# S7CAS-PLEIADES-CARTE-MERE_P01_FPGA-BANK4.net
KiCad netlist of a schematic drawn in Altium Designer
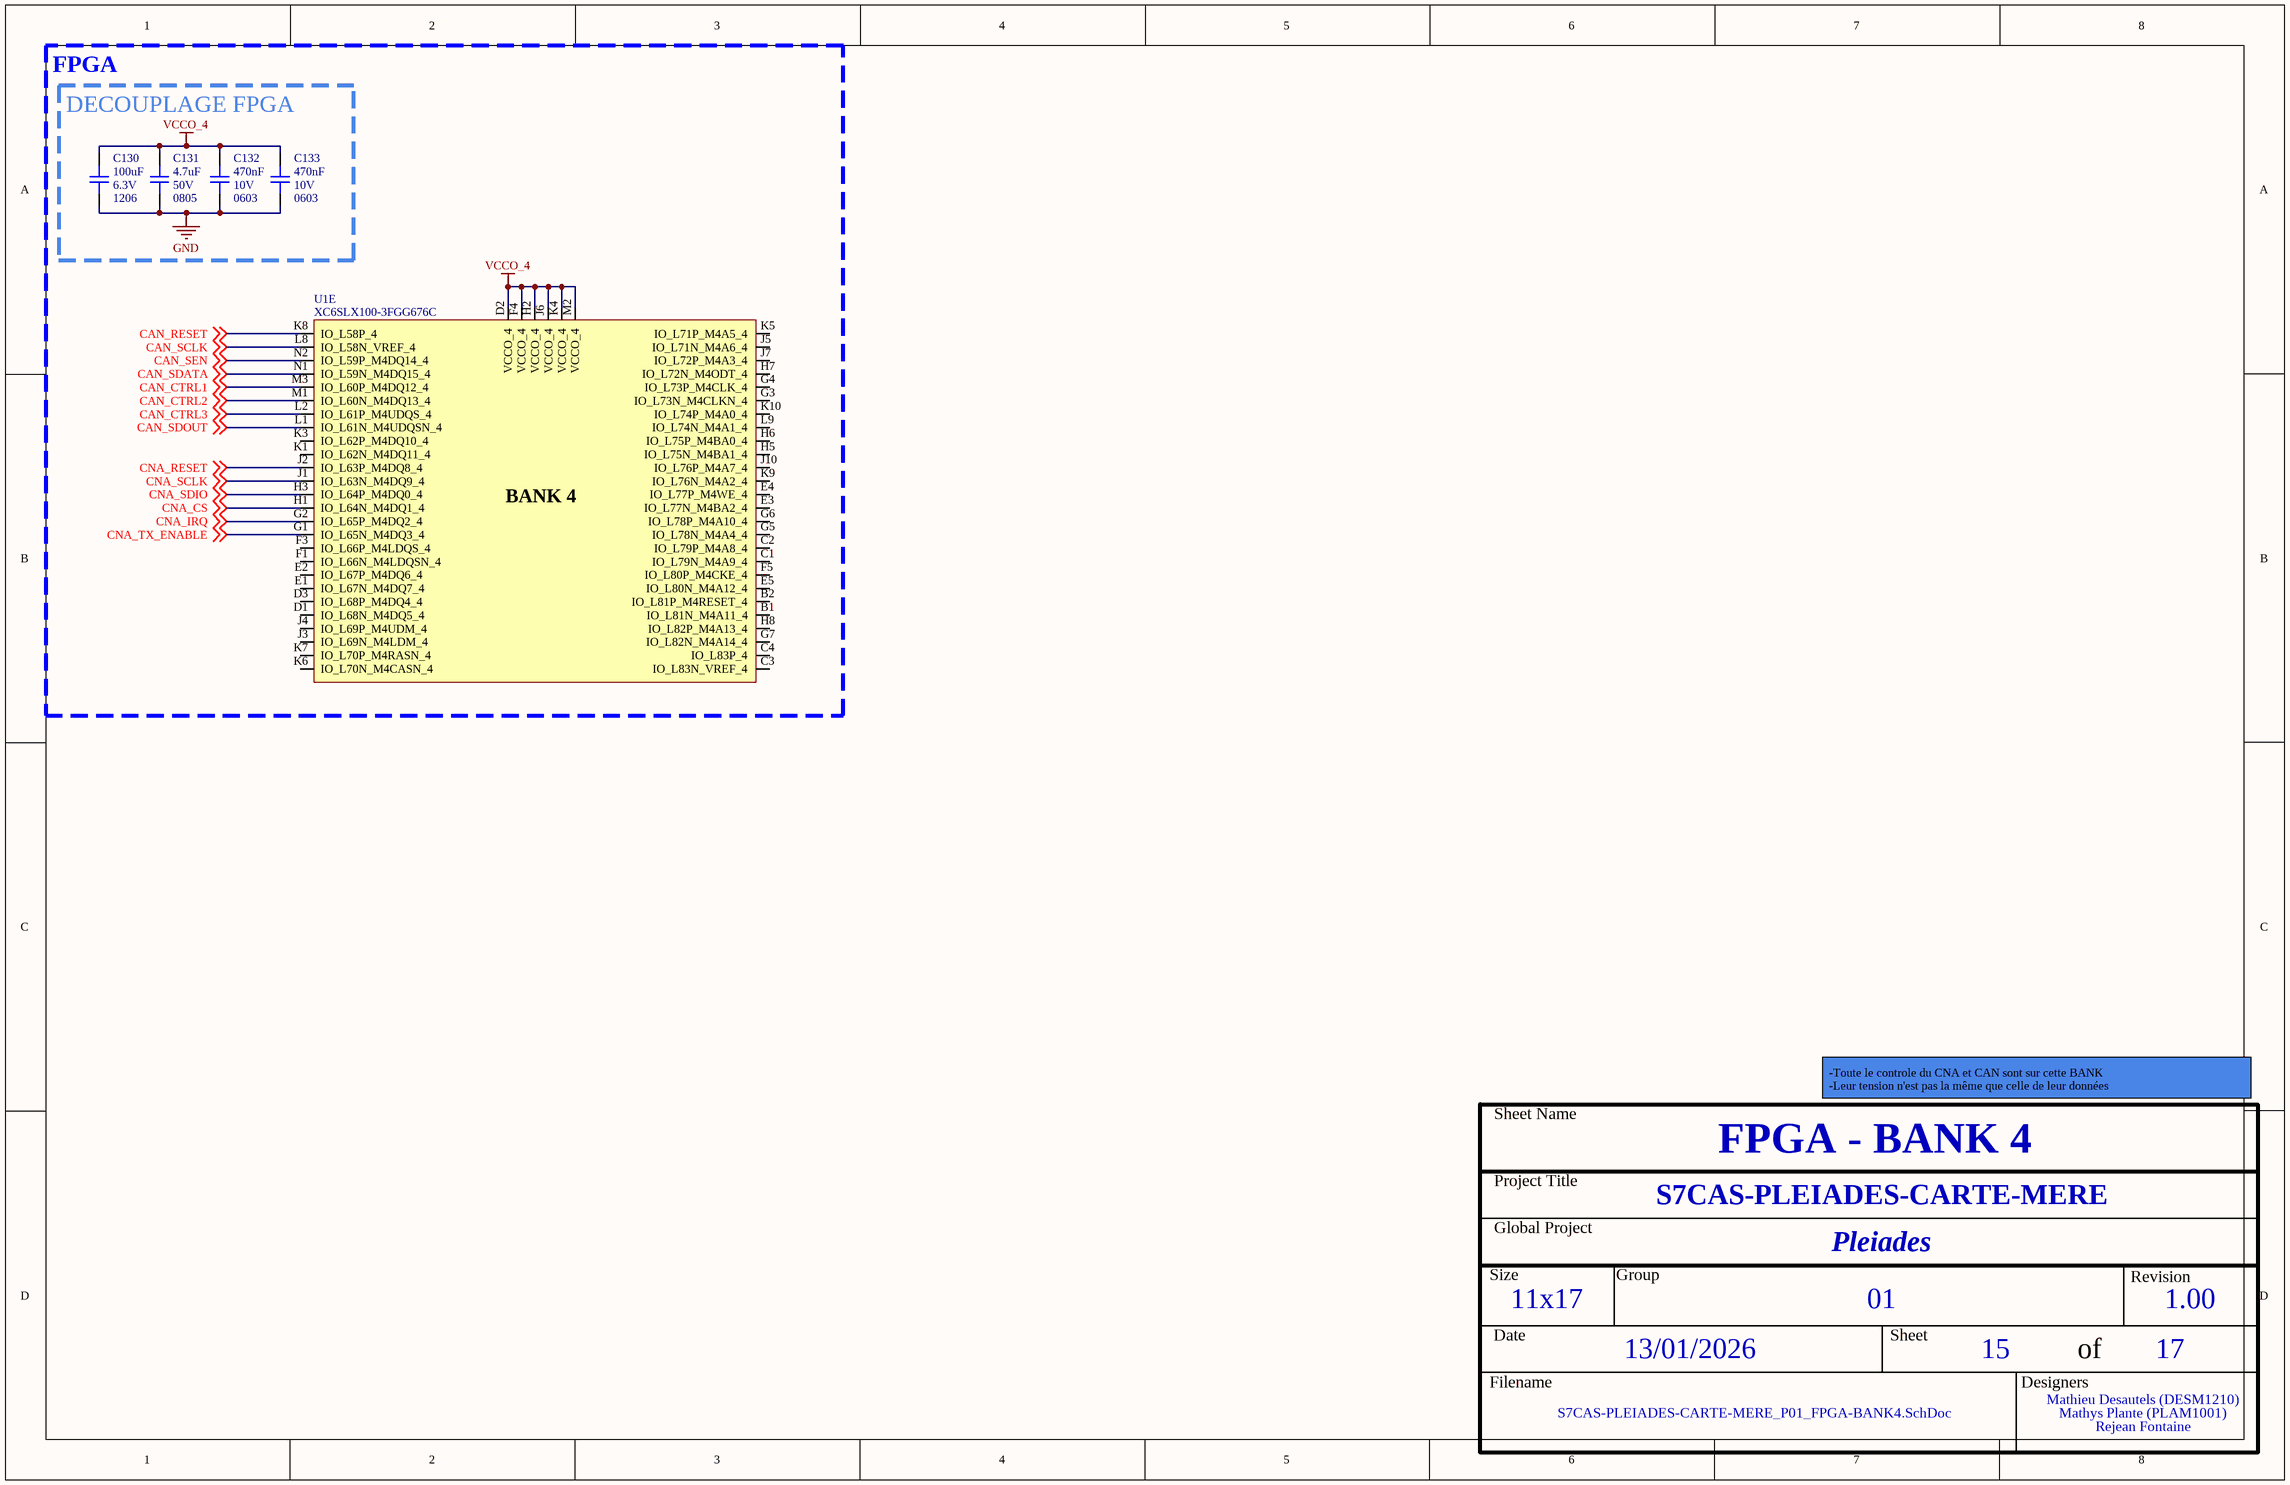
[diagram p0: S7CAS-PLEIADES-CARTE-MERE_P01_FPGA-BANK4.SchDoc]

(export (version "E")
  (design (tool "Eeschema 10.0.6"))
  (components
    (comp (ref "C130")
      (value "100uF")
      (footprint "CAP_1206")
      (description "100 µF ±20% 6.3V Ceramic Capacitor X6T 1206 (3216 Metric)")
      (fields
        (field (name "MFG") "Murata Electronics")
        (field (name "MFG PART NUMBER") "GRM31CD80J107MEA8K")
        (field (name "VOLTAGE") "6.3V")
        (field (name "PACKAGE") "1206")
        (field (name "CREATEDBY") "Jonathan Bouchard")
      )
      (libsource (lib "s7cas_lib2023") (part "CAP - 1206"))
    )
    (comp (ref "C131")
      (value "4.7uF")
      (footprint "CAP_0805")
      (description "4.7 µF ±10% 50V Ceramic Capacitor X5R 0805 (2012 Metric)")
      (fields
        (field (name "MFG") "Murata Electronics")
        (field (name "MFG PART NUMBER") "GRT21BR61H475KE13L")
        (field (name "VOLTAGE") "50V")
        (field (name "PACKAGE") "0805")
        (field (name "CREATEDBY") "Jonathan Bouchard")
      )
      (libsource (lib "s7cas_lib2023") (part "CAP - 0805"))
    )
    (comp (ref "C132")
      (value "470nF")
      (footprint "CAP_0603")
      (description "CAP - 0603")
      (fields
        (field (name "MFG PART NUMBER") "C0603X474K8RAC")
        (field (name "VOLTAGE") "10V")
        (field (name "PACKAGE") "0603")
        (field (name "CREATEDBY") "Jonathan Bouchard")
      )
      (libsource (lib "s7cas_lib2023") (part "CAP - 0603"))
    )
    (comp (ref "C133")
      (value "470nF")
      (footprint "CAP_0603")
      (description "CAP - 0603")
      (fields
        (field (name "MFG PART NUMBER") "C0603X474K8RAC")
        (field (name "VOLTAGE") "10V")
        (field (name "PACKAGE") "0603")
        (field (name "CREATEDBY") "Jonathan Bouchard")
      )
      (libsource (lib "s7cas_lib2023") (part "CAP - 0603"))
    )
    (comp (ref "U1")
      (value "XC6SLX100-3FGG676C")
      (footprint "FPGA_XILINX_FGG676")
      (description "FPGA - XILINX SPARTAN 6 480 I/O - BGA-676")
      (fields
        (field (name "VOLTAGE") "1.14 V ~ 1.26 V")
        (field (name "MFG") "Xilinx")
        (field (name "CREATEDBY") "Jonathan Bouchard")
      )
      (libsource (lib "s7cas_lib2023") (part "FPGA_XC6SLX100-3FGG676C"))
    )
  )
  (nets
    (net (code "1") (name "CAN_CTRL1") (class "Default")
      (node (ref "U1") (pin "M3") (pinfunction "IO_L60P_M4DQ12_4_M3") (pintype "passive"))
    )
    (net (code "2") (name "CAN_CTRL2") (class "Default")
      (node (ref "U1") (pin "M1") (pinfunction "IO_L60N_M4DQ13_4_M1") (pintype "passive"))
    )
    (net (code "3") (name "CAN_CTRL3") (class "Default")
      (node (ref "U1") (pin "L2") (pinfunction "IO_L61P_M4UDQS_4_L2") (pintype "passive"))
    )
    (net (code "4") (name "CAN_RESET") (class "Default")
      (node (ref "U1") (pin "K8") (pinfunction "IO_L58P_4_K8") (pintype "passive"))
    )
    (net (code "5") (name "CAN_SCLK") (class "Default")
      (node (ref "U1") (pin "L8") (pinfunction "IO_L58N_VREF_4_L8") (pintype "passive"))
    )
    (net (code "6") (name "CAN_SDATA") (class "Default")
      (node (ref "U1") (pin "N1") (pinfunction "IO_L59N_M4DQ15_4_N1") (pintype "passive"))
    )
    (net (code "7") (name "CAN_SDOUT") (class "Default")
      (node (ref "U1") (pin "L1") (pinfunction "IO_L61N_M4UDQSN_4_L1") (pintype "passive"))
    )
    (net (code "8") (name "CAN_SEN") (class "Default")
      (node (ref "U1") (pin "N2") (pinfunction "IO_L59P_M4DQ14_4_N2") (pintype "passive"))
    )
    (net (code "9") (name "CNA_CS") (class "Default")
      (node (ref "U1") (pin "H1") (pinfunction "IO_L64N_M4DQ1_4_H1") (pintype "passive"))
    )
    (net (code "10") (name "CNA_IRQ") (class "Default")
      (node (ref "U1") (pin "G2") (pinfunction "IO_L65P_M4DQ2_4_G2") (pintype "passive"))
    )
    (net (code "11") (name "CNA_RESET") (class "Default")
      (node (ref "U1") (pin "J2") (pinfunction "IO_L63P_M4DQ8_4_J2") (pintype "passive"))
    )
    (net (code "12") (name "CNA_SCLK") (class "Default")
      (node (ref "U1") (pin "J1") (pinfunction "IO_L63N_M4DQ9_4_J1") (pintype "passive"))
    )
    (net (code "13") (name "CNA_SDIO") (class "Default")
      (node (ref "U1") (pin "H3") (pinfunction "IO_L64P_M4DQ0_4_H3") (pintype "passive"))
    )
    (net (code "14") (name "CNA_TX_ENABLE") (class "Default")
      (node (ref "U1") (pin "G1") (pinfunction "IO_L65N_M4DQ3_4_G1") (pintype "passive"))
    )
    (net (code "15") (name "GND") (class "Default")
      (node (ref "C130") (pin "1") (pinfunction "1_1") (pintype "passive"))
      (node (ref "C131") (pin "1") (pinfunction "1_1") (pintype "passive"))
      (node (ref "C132") (pin "1") (pinfunction "1_1") (pintype "passive"))
      (node (ref "C133") (pin "1") (pinfunction "1_1") (pintype "passive"))
    )
    (net (code "16") (name "VCCO_4") (class "Default")
      (node (ref "C130") (pin "2") (pinfunction "2_2") (pintype "passive"))
      (node (ref "C131") (pin "2") (pinfunction "2_2") (pintype "passive"))
      (node (ref "C132") (pin "2") (pinfunction "2_2") (pintype "passive"))
      (node (ref "C133") (pin "2") (pinfunction "2_2") (pintype "passive"))
      (node (ref "U1") (pin "D2") (pinfunction "VCCO_4_D2") (pintype "passive"))
      (node (ref "U1") (pin "F4") (pinfunction "VCCO_4_F4") (pintype "passive"))
      (node (ref "U1") (pin "H2") (pinfunction "VCCO_4_H2") (pintype "passive"))
      (node (ref "U1") (pin "J6") (pinfunction "VCCO_4_J6") (pintype "passive"))
      (node (ref "U1") (pin "K4") (pinfunction "VCCO_4_K4") (pintype "passive"))
      (node (ref "U1") (pin "M2") (pinfunction "VCCO_4_M2") (pintype "passive"))
    )
    (net (code "17") (name "unconnected-(U1E-IO_L62N_M4DQ11_4-PadK1)") (class "Default")
      (node (ref "U1") (pin "K1") (pinfunction "IO_L62N_M4DQ11_4_K1") (pintype "passive"))
    )
    (net (code "18") (name "unconnected-(U1E-IO_L62P_M4DQ10_4-PadK3)") (class "Default")
      (node (ref "U1") (pin "K3") (pinfunction "IO_L62P_M4DQ10_4_K3") (pintype "passive"))
    )
    (net (code "19") (name "unconnected-(U1E-IO_L66N_M4LDQSN_4-PadF1)") (class "Default")
      (node (ref "U1") (pin "F1") (pinfunction "IO_L66N_M4LDQSN_4_F1") (pintype "passive"))
    )
    (net (code "20") (name "unconnected-(U1E-IO_L66P_M4LDQS_4-PadF3)") (class "Default")
      (node (ref "U1") (pin "F3") (pinfunction "IO_L66P_M4LDQS_4_F3") (pintype "passive"))
    )
    (net (code "21") (name "unconnected-(U1E-IO_L67N_M4DQ7_4-PadE1)") (class "Default")
      (node (ref "U1") (pin "E1") (pinfunction "IO_L67N_M4DQ7_4_E1") (pintype "passive"))
    )
    (net (code "22") (name "unconnected-(U1E-IO_L67P_M4DQ6_4-PadE2)") (class "Default")
      (node (ref "U1") (pin "E2") (pinfunction "IO_L67P_M4DQ6_4_E2") (pintype "passive"))
    )
    (net (code "23") (name "unconnected-(U1E-IO_L68N_M4DQ5_4-PadD1)") (class "Default")
      (node (ref "U1") (pin "D1") (pinfunction "IO_L68N_M4DQ5_4_D1") (pintype "passive"))
    )
    (net (code "24") (name "unconnected-(U1E-IO_L68P_M4DQ4_4-PadD3)") (class "Default")
      (node (ref "U1") (pin "D3") (pinfunction "IO_L68P_M4DQ4_4_D3") (pintype "passive"))
    )
    (net (code "25") (name "unconnected-(U1E-IO_L69N_M4LDM_4-PadJ3)") (class "Default")
      (node (ref "U1") (pin "J3") (pinfunction "IO_L69N_M4LDM_4_J3") (pintype "passive"))
    )
    (net (code "26") (name "unconnected-(U1E-IO_L69P_M4UDM_4-PadJ4)") (class "Default")
      (node (ref "U1") (pin "J4") (pinfunction "IO_L69P_M4UDM_4_J4") (pintype "passive"))
    )
    (net (code "27") (name "unconnected-(U1E-IO_L70N_M4CASN_4-PadK6)") (class "Default")
      (node (ref "U1") (pin "K6") (pinfunction "IO_L70N_M4CASN_4_K6") (pintype "passive"))
    )
    (net (code "28") (name "unconnected-(U1E-IO_L70P_M4RASN_4-PadK7)") (class "Default")
      (node (ref "U1") (pin "K7") (pinfunction "IO_L70P_M4RASN_4_K7") (pintype "passive"))
    )
    (net (code "29") (name "unconnected-(U1E-IO_L71N_M4A6_4-PadJ5)") (class "Default")
      (node (ref "U1") (pin "J5") (pinfunction "IO_L71N_M4A6_4_J5") (pintype "passive"))
    )
    (net (code "30") (name "unconnected-(U1E-IO_L71P_M4A5_4-PadK5)") (class "Default")
      (node (ref "U1") (pin "K5") (pinfunction "IO_L71P_M4A5_4_K5") (pintype "passive"))
    )
    (net (code "31") (name "unconnected-(U1E-IO_L72N_M4ODT_4-PadH7)") (class "Default")
      (node (ref "U1") (pin "H7") (pinfunction "IO_L72N_M4ODT_4_H7") (pintype "passive"))
    )
    (net (code "32") (name "unconnected-(U1E-IO_L72P_M4A3_4-PadJ7)") (class "Default")
      (node (ref "U1") (pin "J7") (pinfunction "IO_L72P_M4A3_4_J7") (pintype "passive"))
    )
    (net (code "33") (name "unconnected-(U1E-IO_L73N_M4CLKN_4-PadG3)") (class "Default")
      (node (ref "U1") (pin "G3") (pinfunction "IO_L73N_M4CLKN_4_G3") (pintype "passive"))
    )
    (net (code "34") (name "unconnected-(U1E-IO_L73P_M4CLK_4-PadG4)") (class "Default")
      (node (ref "U1") (pin "G4") (pinfunction "IO_L73P_M4CLK_4_G4") (pintype "passive"))
    )
    (net (code "35") (name "unconnected-(U1E-IO_L74N_M4A1_4-PadL9)") (class "Default")
      (node (ref "U1") (pin "L9") (pinfunction "IO_L74N_M4A1_4_L9") (pintype "passive"))
    )
    (net (code "36") (name "unconnected-(U1E-IO_L74P_M4A0_4-PadK10)") (class "Default")
      (node (ref "U1") (pin "K10") (pinfunction "IO_L74P_M4A0_4_K10") (pintype "passive"))
    )
    (net (code "37") (name "unconnected-(U1E-IO_L75N_M4BA1_4-PadH5)") (class "Default")
      (node (ref "U1") (pin "H5") (pinfunction "IO_L75N_M4BA1_4_H5") (pintype "passive"))
    )
    (net (code "38") (name "unconnected-(U1E-IO_L75P_M4BA0_4-PadH6)") (class "Default")
      (node (ref "U1") (pin "H6") (pinfunction "IO_L75P_M4BA0_4_H6") (pintype "passive"))
    )
    (net (code "39") (name "unconnected-(U1E-IO_L76N_M4A2_4-PadK9)") (class "Default")
      (node (ref "U1") (pin "K9") (pinfunction "IO_L76N_M4A2_4_K9") (pintype "passive"))
    )
    (net (code "40") (name "unconnected-(U1E-IO_L76P_M4A7_4-PadJ10)") (class "Default")
      (node (ref "U1") (pin "J10") (pinfunction "IO_L76P_M4A7_4_J10") (pintype "passive"))
    )
    (net (code "41") (name "unconnected-(U1E-IO_L77N_M4BA2_4-PadE3)") (class "Default")
      (node (ref "U1") (pin "E3") (pinfunction "IO_L77N_M4BA2_4_E3") (pintype "passive"))
    )
    (net (code "42") (name "unconnected-(U1E-IO_L77P_M4WE_4-PadE4)") (class "Default")
      (node (ref "U1") (pin "E4") (pinfunction "IO_L77P_M4WE_4_E4") (pintype "passive"))
    )
    (net (code "43") (name "unconnected-(U1E-IO_L78N_M4A4_4-PadG5)") (class "Default")
      (node (ref "U1") (pin "G5") (pinfunction "IO_L78N_M4A4_4_G5") (pintype "passive"))
    )
    (net (code "44") (name "unconnected-(U1E-IO_L78P_M4A10_4-PadG6)") (class "Default")
      (node (ref "U1") (pin "G6") (pinfunction "IO_L78P_M4A10_4_G6") (pintype "passive"))
    )
    (net (code "45") (name "unconnected-(U1E-IO_L79N_M4A9_4-PadC1)") (class "Default")
      (node (ref "U1") (pin "C1") (pinfunction "IO_L79N_M4A9_4_C1") (pintype "passive"))
    )
    (net (code "46") (name "unconnected-(U1E-IO_L79P_M4A8_4-PadC2)") (class "Default")
      (node (ref "U1") (pin "C2") (pinfunction "IO_L79P_M4A8_4_C2") (pintype "passive"))
    )
    (net (code "47") (name "unconnected-(U1E-IO_L80N_M4A12_4-PadE5)") (class "Default")
      (node (ref "U1") (pin "E5") (pinfunction "IO_L80N_M4A12_4_E5") (pintype "passive"))
    )
    (net (code "48") (name "unconnected-(U1E-IO_L80P_M4CKE_4-PadF5)") (class "Default")
      (node (ref "U1") (pin "F5") (pinfunction "IO_L80P_M4CKE_4_F5") (pintype "passive"))
    )
    (net (code "49") (name "unconnected-(U1E-IO_L81N_M4A11_4-PadB1)") (class "Default")
      (node (ref "U1") (pin "B1") (pinfunction "IO_L81N_M4A11_4_B1") (pintype "passive"))
    )
    (net (code "50") (name "unconnected-(U1E-IO_L81P_M4RESET_4-PadB2)") (class "Default")
      (node (ref "U1") (pin "B2") (pinfunction "IO_L81P_M4RESET_4_B2") (pintype "passive"))
    )
    (net (code "51") (name "unconnected-(U1E-IO_L82N_M4A14_4-PadG7)") (class "Default")
      (node (ref "U1") (pin "G7") (pinfunction "IO_L82N_M4A14_4_G7") (pintype "passive"))
    )
    (net (code "52") (name "unconnected-(U1E-IO_L82P_M4A13_4-PadH8)") (class "Default")
      (node (ref "U1") (pin "H8") (pinfunction "IO_L82P_M4A13_4_H8") (pintype "passive"))
    )
    (net (code "53") (name "unconnected-(U1E-IO_L83N_VREF_4-PadC3)") (class "Default")
      (node (ref "U1") (pin "C3") (pinfunction "IO_L83N_VREF_4_C3") (pintype "passive"))
    )
    (net (code "54") (name "unconnected-(U1E-IO_L83P_4-PadC4)") (class "Default")
      (node (ref "U1") (pin "C4") (pinfunction "IO_L83P_4_C4") (pintype "passive"))
    )
  )
)
